# JackPots.net
KiCad netlist of a schematic drawn in EAGLE
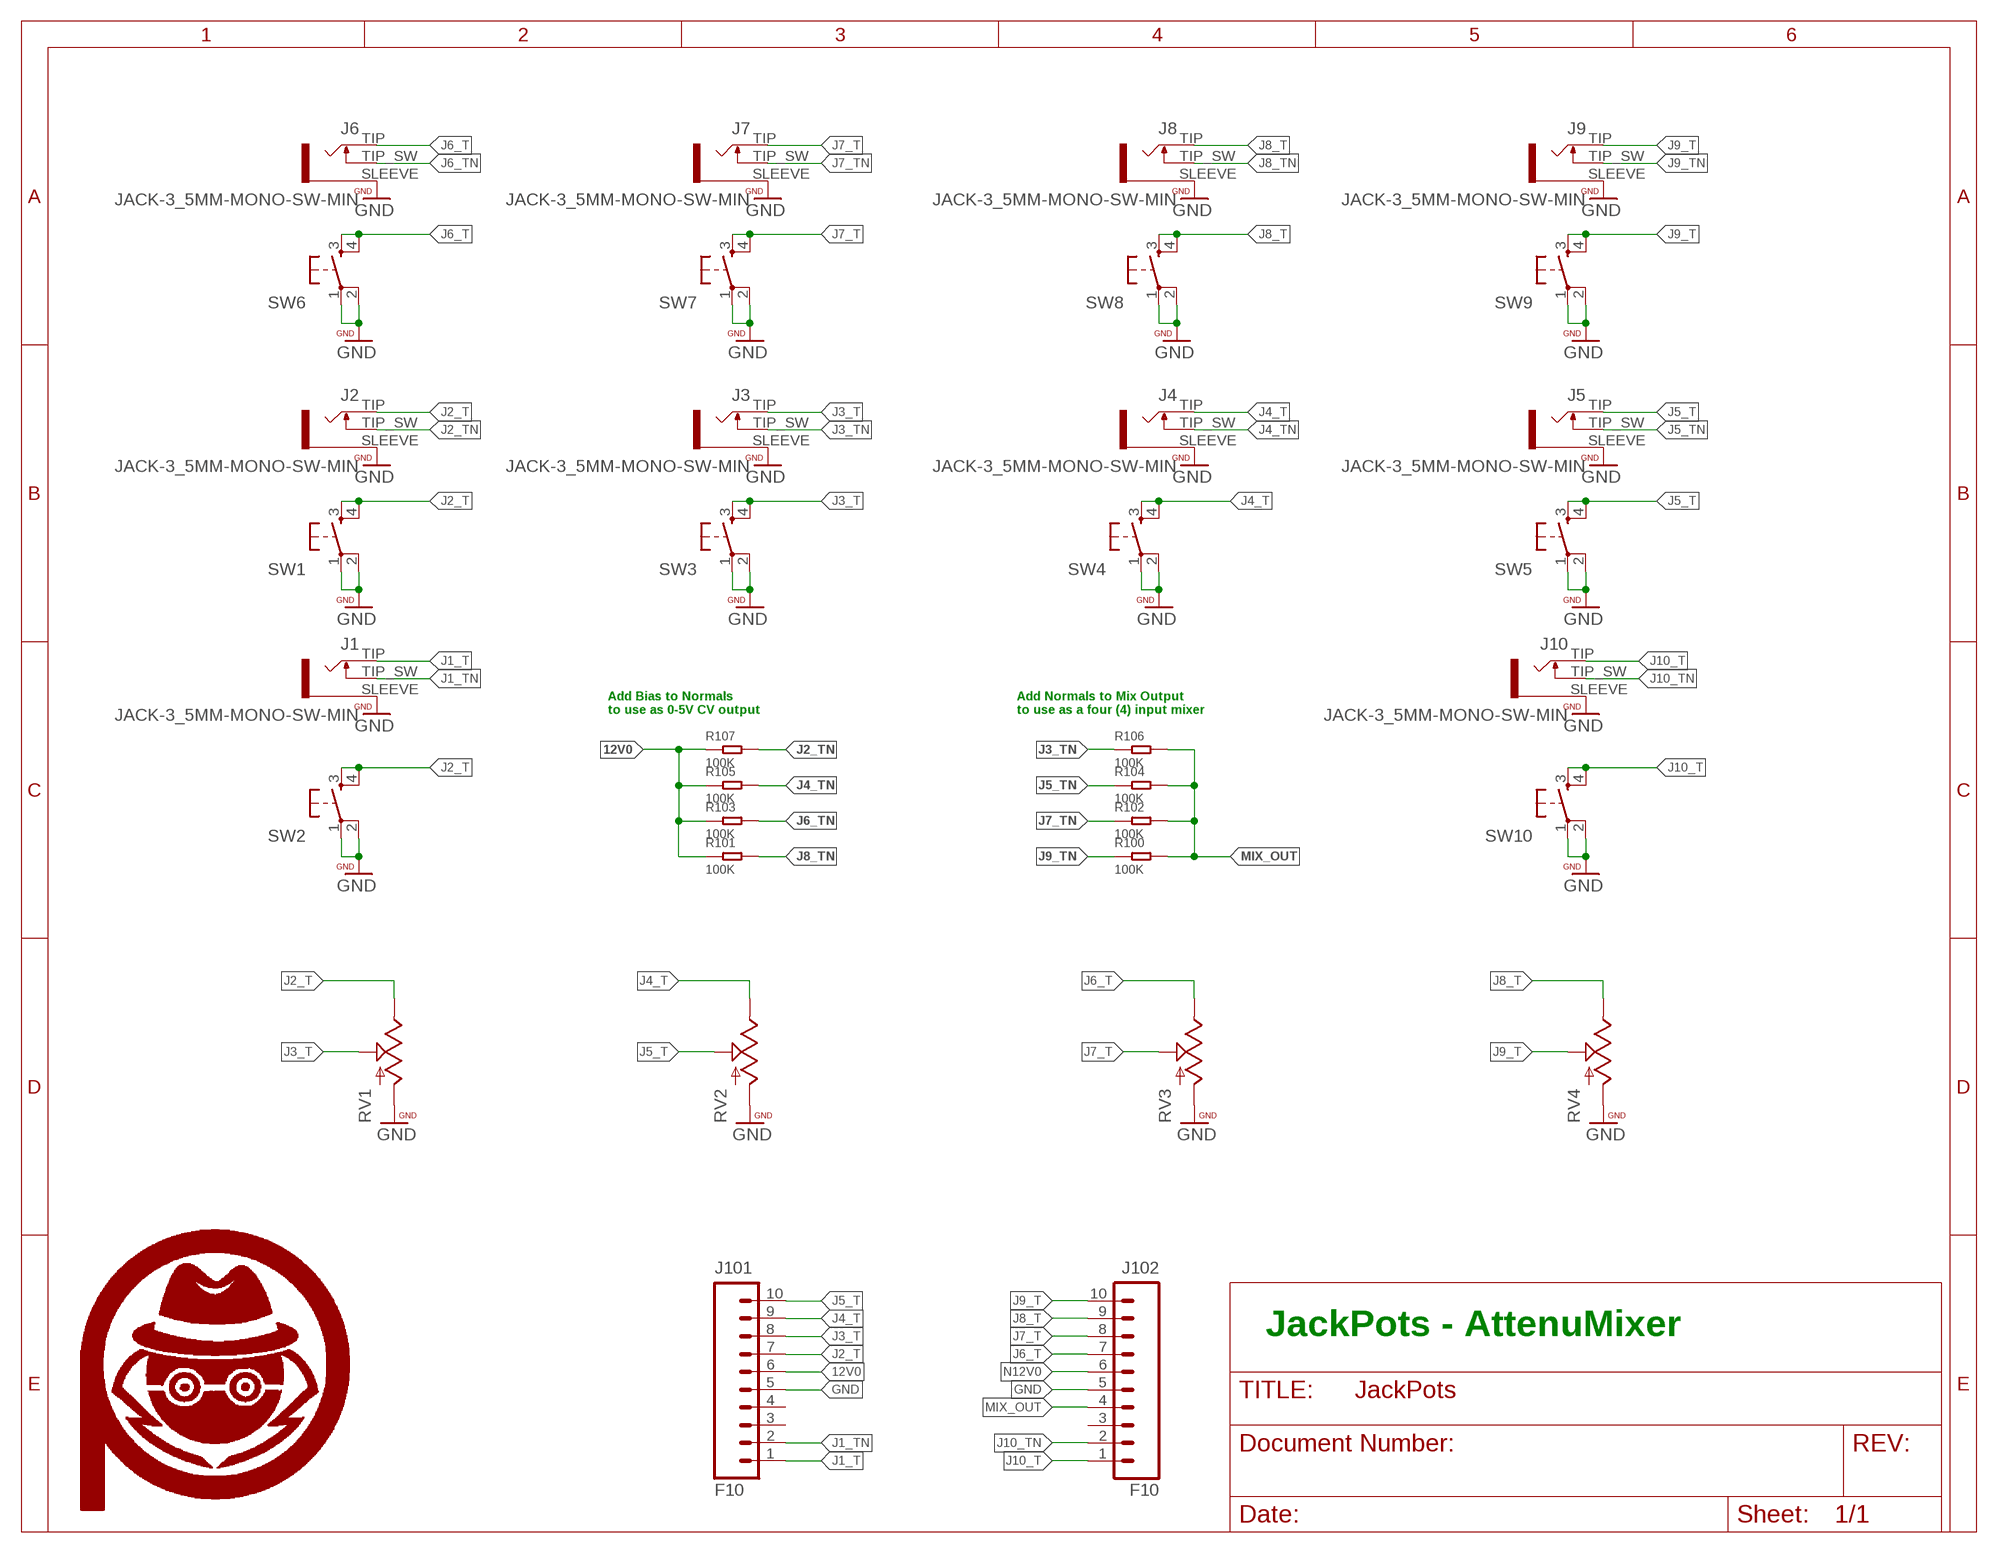
[diagram p0: schematic, sheet 1]

(export (version "E")
  (design (tool "Eeschema 10.0.6"))
  (components
    (comp (ref "$$U$1")
      (value "PA_LOGO_SYMSMALL")
      (footprint "eagle-import:PA_LOGO_AGENT_SMALL_SYM")
      (libsource (lib "eagle-import") (part "PA_LOGO_SYMSMALL"))
    )
    (comp (ref "$$U$100")
      (value "PA_LOGO_SYMMED")
      (footprint "eagle-import:PA_LOGO_AGENT_MED_SYM")
      (libsource (lib "eagle-import") (part "PA_LOGO_SYMMED"))
    )
    (comp (ref "$$U$101")
      (value "PA_LOGO_SYMMED")
      (footprint "eagle-import:PA_LOGO_AGENT_MED_SYM")
      (libsource (lib "eagle-import") (part "PA_LOGO_SYMMED"))
    )
    (comp (ref "J1")
      (value "JACK-3_5MM-MONO-SW-MIN")
      (footprint "eagle-import:WQP_PJ301M-MIN")
      (libsource (lib "eagle-import") (part "JACK-3_5MM-MONO-SW-MIN"))
    )
    (comp (ref "J2")
      (value "JACK-3_5MM-MONO-SW-MIN")
      (footprint "eagle-import:WQP_PJ301M-MIN")
      (libsource (lib "eagle-import") (part "JACK-3_5MM-MONO-SW-MIN"))
    )
    (comp (ref "J3")
      (value "JACK-3_5MM-MONO-SW-MIN")
      (footprint "eagle-import:WQP_PJ301M-MIN")
      (libsource (lib "eagle-import") (part "JACK-3_5MM-MONO-SW-MIN"))
    )
    (comp (ref "J4")
      (value "JACK-3_5MM-MONO-SW-MIN")
      (footprint "eagle-import:WQP_PJ301M-MIN")
      (libsource (lib "eagle-import") (part "JACK-3_5MM-MONO-SW-MIN"))
    )
    (comp (ref "J5")
      (value "JACK-3_5MM-MONO-SW-MIN")
      (footprint "eagle-import:WQP_PJ301M-MIN")
      (libsource (lib "eagle-import") (part "JACK-3_5MM-MONO-SW-MIN"))
    )
    (comp (ref "J6")
      (value "JACK-3_5MM-MONO-SW-MIN")
      (footprint "eagle-import:WQP_PJ301M-MIN")
      (libsource (lib "eagle-import") (part "JACK-3_5MM-MONO-SW-MIN"))
    )
    (comp (ref "J7")
      (value "JACK-3_5MM-MONO-SW-MIN")
      (footprint "eagle-import:WQP_PJ301M-MIN")
      (libsource (lib "eagle-import") (part "JACK-3_5MM-MONO-SW-MIN"))
    )
    (comp (ref "J8")
      (value "JACK-3_5MM-MONO-SW-MIN")
      (footprint "eagle-import:WQP_PJ301M-MIN")
      (libsource (lib "eagle-import") (part "JACK-3_5MM-MONO-SW-MIN"))
    )
    (comp (ref "J9")
      (value "JACK-3_5MM-MONO-SW-MIN")
      (footprint "eagle-import:WQP_PJ301M-MIN")
      (libsource (lib "eagle-import") (part "JACK-3_5MM-MONO-SW-MIN"))
    )
    (comp (ref "J10")
      (value "JACK-3_5MM-MONO-SW-MIN")
      (footprint "eagle-import:WQP_PJ301M-MIN")
      (libsource (lib "eagle-import") (part "JACK-3_5MM-MONO-SW-MIN"))
    )
    (comp (ref "J101")
      (value "F10")
      (footprint "eagle-import:1X10_OCTO")
      (libsource (lib "eagle-import") (part "M10SILK_FEMALE_PTH"))
    )
    (comp (ref "J102")
      (value "F10")
      (footprint "eagle-import:1X10_OCTO")
      (libsource (lib "eagle-import") (part "M10SILK_FEMALE_PTH"))
    )
    (comp (ref "R100")
      (value "100K")
      (footprint "eagle-import:R0603")
      (fields (field (name "MPN") "RC0603FR-07100KL"))
      (libsource (lib "eagle-import") (part "SMD-RES-100K-1%-1/10W(0603)"))
    )
    (comp (ref "R101")
      (value "100K")
      (footprint "eagle-import:R0603")
      (fields (field (name "MPN") "RC0603FR-07100KL"))
      (libsource (lib "eagle-import") (part "SMD-RES-100K-1%-1/10W(0603)"))
    )
    (comp (ref "R102")
      (value "100K")
      (footprint "eagle-import:R0603")
      (fields (field (name "MPN") "RC0603FR-07100KL"))
      (libsource (lib "eagle-import") (part "SMD-RES-100K-1%-1/10W(0603)"))
    )
    (comp (ref "R103")
      (value "100K")
      (footprint "eagle-import:R0603")
      (fields (field (name "MPN") "RC0603FR-07100KL"))
      (libsource (lib "eagle-import") (part "SMD-RES-100K-1%-1/10W(0603)"))
    )
    (comp (ref "R104")
      (value "100K")
      (footprint "eagle-import:R0603")
      (fields (field (name "MPN") "RC0603FR-07100KL"))
      (libsource (lib "eagle-import") (part "SMD-RES-100K-1%-1/10W(0603)"))
    )
    (comp (ref "R105")
      (value "100K")
      (footprint "eagle-import:R0603")
      (fields (field (name "MPN") "RC0603FR-07100KL"))
      (libsource (lib "eagle-import") (part "SMD-RES-100K-1%-1/10W(0603)"))
    )
    (comp (ref "R106")
      (value "100K")
      (footprint "eagle-import:R0603")
      (fields (field (name "MPN") "RC0603FR-07100KL"))
      (libsource (lib "eagle-import") (part "SMD-RES-100K-1%-1/10W(0603)"))
    )
    (comp (ref "R107")
      (value "100K")
      (footprint "eagle-import:R0603")
      (fields (field (name "MPN") "RC0603FR-07100KL"))
      (libsource (lib "eagle-import") (part "SMD-RES-100K-1%-1/10W(0603)"))
    )
    (comp (ref "RV1")
      (value "POT")
      (footprint "eagle-import:ALPS_POT")
      (libsource (lib "eagle-import") (part "POT"))
    )
    (comp (ref "RV2")
      (value "POT")
      (footprint "eagle-import:ALPS_POT")
      (libsource (lib "eagle-import") (part "POT"))
    )
    (comp (ref "RV3")
      (value "POT")
      (footprint "eagle-import:ALPS_POT")
      (libsource (lib "eagle-import") (part "POT"))
    )
    (comp (ref "RV4")
      (value "POT")
      (footprint "eagle-import:ALPS_POT")
      (libsource (lib "eagle-import") (part "POT"))
    )
    (comp (ref "SW1")
      (value "TAC_SWITCHPTH")
      (footprint "eagle-import:TACTILE-PTH")
      (libsource (lib "eagle-import") (part "TAC_SWITCHPTH"))
    )
    (comp (ref "SW2")
      (value "TAC_SWITCHPTH")
      (footprint "eagle-import:TACTILE-PTH")
      (libsource (lib "eagle-import") (part "TAC_SWITCHPTH"))
    )
    (comp (ref "SW3")
      (value "TAC_SWITCHPTH")
      (footprint "eagle-import:TACTILE-PTH")
      (libsource (lib "eagle-import") (part "TAC_SWITCHPTH"))
    )
    (comp (ref "SW4")
      (value "TAC_SWITCHPTH")
      (footprint "eagle-import:TACTILE-PTH")
      (libsource (lib "eagle-import") (part "TAC_SWITCHPTH"))
    )
    (comp (ref "SW5")
      (value "TAC_SWITCHPTH")
      (footprint "eagle-import:TACTILE-PTH")
      (libsource (lib "eagle-import") (part "TAC_SWITCHPTH"))
    )
    (comp (ref "SW6")
      (value "TAC_SWITCHPTH")
      (footprint "eagle-import:TACTILE-PTH")
      (libsource (lib "eagle-import") (part "TAC_SWITCHPTH"))
    )
    (comp (ref "SW7")
      (value "TAC_SWITCHPTH")
      (footprint "eagle-import:TACTILE-PTH")
      (libsource (lib "eagle-import") (part "TAC_SWITCHPTH"))
    )
    (comp (ref "SW8")
      (value "TAC_SWITCHPTH")
      (footprint "eagle-import:TACTILE-PTH")
      (libsource (lib "eagle-import") (part "TAC_SWITCHPTH"))
    )
    (comp (ref "SW9")
      (value "TAC_SWITCHPTH")
      (footprint "eagle-import:TACTILE-PTH")
      (libsource (lib "eagle-import") (part "TAC_SWITCHPTH"))
    )
    (comp (ref "SW10")
      (value "TAC_SWITCHPTH")
      (footprint "eagle-import:TACTILE-PTH")
      (libsource (lib "eagle-import") (part "TAC_SWITCHPTH"))
    )
  )
  (nets
    (net (code "1") (name "12V0") (class "Default")
      (node (ref "J101") (pin "6") (pinfunction "6_6") (pintype "passive"))
      (node (ref "R101") (pin "1") (pinfunction "1_1") (pintype "passive"))
      (node (ref "R103") (pin "1") (pinfunction "1_1") (pintype "passive"))
      (node (ref "R105") (pin "1") (pinfunction "1_1") (pintype "passive"))
      (node (ref "R107") (pin "1") (pinfunction "1_1") (pintype "passive"))
    )
    (net (code "2") (name "GND") (class "Default")
      (node (ref "J1") (pin "SLEEVE") (pinfunction "SLEEVE_SLEEVE") (pintype "passive"))
      (node (ref "J10") (pin "SLEEVE") (pinfunction "SLEEVE_SLEEVE") (pintype "passive"))
      (node (ref "J101") (pin "5") (pinfunction "5_5") (pintype "passive"))
      (node (ref "J102") (pin "5") (pinfunction "5_5") (pintype "passive"))
      (node (ref "J2") (pin "SLEEVE") (pinfunction "SLEEVE_SLEEVE") (pintype "passive"))
      (node (ref "J3") (pin "SLEEVE") (pinfunction "SLEEVE_SLEEVE") (pintype "passive"))
      (node (ref "J4") (pin "SLEEVE") (pinfunction "SLEEVE_SLEEVE") (pintype "passive"))
      (node (ref "J5") (pin "SLEEVE") (pinfunction "SLEEVE_SLEEVE") (pintype "passive"))
      (node (ref "J6") (pin "SLEEVE") (pinfunction "SLEEVE_SLEEVE") (pintype "passive"))
      (node (ref "J7") (pin "SLEEVE") (pinfunction "SLEEVE_SLEEVE") (pintype "passive"))
      (node (ref "J8") (pin "SLEEVE") (pinfunction "SLEEVE_SLEEVE") (pintype "passive"))
      (node (ref "J9") (pin "SLEEVE") (pinfunction "SLEEVE_SLEEVE") (pintype "passive"))
      (node (ref "RV1") (pin "P$3") (pinfunction "1_P$3") (pintype "passive"))
      (node (ref "RV2") (pin "P$3") (pinfunction "1_P$3") (pintype "passive"))
      (node (ref "RV3") (pin "P$3") (pinfunction "1_P$3") (pintype "passive"))
      (node (ref "RV4") (pin "P$3") (pinfunction "1_P$3") (pintype "passive"))
      (node (ref "SW1") (pin "1") (pinfunction "1_1") (pintype "passive"))
      (node (ref "SW1") (pin "2") (pinfunction "2_2") (pintype "passive"))
      (node (ref "SW10") (pin "1") (pinfunction "1_1") (pintype "passive"))
      (node (ref "SW10") (pin "2") (pinfunction "2_2") (pintype "passive"))
      (node (ref "SW2") (pin "1") (pinfunction "1_1") (pintype "passive"))
      (node (ref "SW2") (pin "2") (pinfunction "2_2") (pintype "passive"))
      (node (ref "SW3") (pin "1") (pinfunction "1_1") (pintype "passive"))
      (node (ref "SW3") (pin "2") (pinfunction "2_2") (pintype "passive"))
      (node (ref "SW4") (pin "1") (pinfunction "1_1") (pintype "passive"))
      (node (ref "SW4") (pin "2") (pinfunction "2_2") (pintype "passive"))
      (node (ref "SW5") (pin "1") (pinfunction "1_1") (pintype "passive"))
      (node (ref "SW5") (pin "2") (pinfunction "2_2") (pintype "passive"))
      (node (ref "SW6") (pin "1") (pinfunction "1_1") (pintype "passive"))
      (node (ref "SW6") (pin "2") (pinfunction "2_2") (pintype "passive"))
      (node (ref "SW7") (pin "1") (pinfunction "1_1") (pintype "passive"))
      (node (ref "SW7") (pin "2") (pinfunction "2_2") (pintype "passive"))
      (node (ref "SW8") (pin "1") (pinfunction "1_1") (pintype "passive"))
      (node (ref "SW8") (pin "2") (pinfunction "2_2") (pintype "passive"))
      (node (ref "SW9") (pin "1") (pinfunction "1_1") (pintype "passive"))
      (node (ref "SW9") (pin "2") (pinfunction "2_2") (pintype "passive"))
    )
    (net (code "3") (name "J1_T") (class "Default")
      (node (ref "J1") (pin "TIP") (pinfunction "TIP_TIP") (pintype "passive"))
      (node (ref "J101") (pin "1") (pinfunction "1_1") (pintype "passive"))
    )
    (net (code "4") (name "J1_TN") (class "Default")
      (node (ref "J1") (pin "TIP_SW") (pinfunction "TIP_SW_TIP_SW") (pintype "passive"))
      (node (ref "J101") (pin "2") (pinfunction "2_2") (pintype "passive"))
    )
    (net (code "5") (name "J2_T") (class "Default")
      (node (ref "J101") (pin "7") (pinfunction "7_7") (pintype "passive"))
      (node (ref "J2") (pin "TIP") (pinfunction "TIP_TIP") (pintype "passive"))
      (node (ref "RV1") (pin "P$1") (pinfunction "3_P$1") (pintype "passive"))
      (node (ref "SW1") (pin "3") (pinfunction "3_3") (pintype "passive"))
      (node (ref "SW1") (pin "4") (pinfunction "4_4") (pintype "passive"))
      (node (ref "SW2") (pin "3") (pinfunction "3_3") (pintype "passive"))
      (node (ref "SW2") (pin "4") (pinfunction "4_4") (pintype "passive"))
    )
    (net (code "6") (name "J2_TN") (class "Default")
      (node (ref "J2") (pin "TIP_SW") (pinfunction "TIP_SW_TIP_SW") (pintype "passive"))
      (node (ref "R107") (pin "2") (pinfunction "2_2") (pintype "passive"))
    )
    (net (code "7") (name "J3_T") (class "Default")
      (node (ref "J101") (pin "8") (pinfunction "8_8") (pintype "passive"))
      (node (ref "J3") (pin "TIP") (pinfunction "TIP_TIP") (pintype "passive"))
      (node (ref "RV1") (pin "P$2") (pinfunction "2_P$2") (pintype "passive"))
      (node (ref "SW3") (pin "3") (pinfunction "3_3") (pintype "passive"))
      (node (ref "SW3") (pin "4") (pinfunction "4_4") (pintype "passive"))
    )
    (net (code "8") (name "J3_TN") (class "Default")
      (node (ref "J3") (pin "TIP_SW") (pinfunction "TIP_SW_TIP_SW") (pintype "passive"))
      (node (ref "R106") (pin "1") (pinfunction "1_1") (pintype "passive"))
    )
    (net (code "9") (name "J4_T") (class "Default")
      (node (ref "J101") (pin "9") (pinfunction "9_9") (pintype "passive"))
      (node (ref "J4") (pin "TIP") (pinfunction "TIP_TIP") (pintype "passive"))
      (node (ref "RV2") (pin "P$1") (pinfunction "3_P$1") (pintype "passive"))
      (node (ref "SW4") (pin "3") (pinfunction "3_3") (pintype "passive"))
      (node (ref "SW4") (pin "4") (pinfunction "4_4") (pintype "passive"))
    )
    (net (code "10") (name "J4_TN") (class "Default")
      (node (ref "J4") (pin "TIP_SW") (pinfunction "TIP_SW_TIP_SW") (pintype "passive"))
      (node (ref "R105") (pin "2") (pinfunction "2_2") (pintype "passive"))
    )
    (net (code "11") (name "J5_T") (class "Default")
      (node (ref "J101") (pin "10") (pinfunction "10_10") (pintype "passive"))
      (node (ref "J5") (pin "TIP") (pinfunction "TIP_TIP") (pintype "passive"))
      (node (ref "RV2") (pin "P$2") (pinfunction "2_P$2") (pintype "passive"))
      (node (ref "SW5") (pin "3") (pinfunction "3_3") (pintype "passive"))
      (node (ref "SW5") (pin "4") (pinfunction "4_4") (pintype "passive"))
    )
    (net (code "12") (name "J5_TN") (class "Default")
      (node (ref "J5") (pin "TIP_SW") (pinfunction "TIP_SW_TIP_SW") (pintype "passive"))
      (node (ref "R104") (pin "1") (pinfunction "1_1") (pintype "passive"))
    )
    (net (code "13") (name "J6_T") (class "Default")
      (node (ref "J102") (pin "7") (pinfunction "7_7") (pintype "passive"))
      (node (ref "J6") (pin "TIP") (pinfunction "TIP_TIP") (pintype "passive"))
      (node (ref "RV3") (pin "P$1") (pinfunction "3_P$1") (pintype "passive"))
      (node (ref "SW6") (pin "3") (pinfunction "3_3") (pintype "passive"))
      (node (ref "SW6") (pin "4") (pinfunction "4_4") (pintype "passive"))
    )
    (net (code "14") (name "J6_TN") (class "Default")
      (node (ref "J6") (pin "TIP_SW") (pinfunction "TIP_SW_TIP_SW") (pintype "passive"))
      (node (ref "R103") (pin "2") (pinfunction "2_2") (pintype "passive"))
    )
    (net (code "15") (name "J7_T") (class "Default")
      (node (ref "J102") (pin "8") (pinfunction "8_8") (pintype "passive"))
      (node (ref "J7") (pin "TIP") (pinfunction "TIP_TIP") (pintype "passive"))
      (node (ref "RV3") (pin "P$2") (pinfunction "2_P$2") (pintype "passive"))
      (node (ref "SW7") (pin "3") (pinfunction "3_3") (pintype "passive"))
      (node (ref "SW7") (pin "4") (pinfunction "4_4") (pintype "passive"))
    )
    (net (code "16") (name "J7_TN") (class "Default")
      (node (ref "J7") (pin "TIP_SW") (pinfunction "TIP_SW_TIP_SW") (pintype "passive"))
      (node (ref "R102") (pin "1") (pinfunction "1_1") (pintype "passive"))
    )
    (net (code "17") (name "J8_T") (class "Default")
      (node (ref "J102") (pin "9") (pinfunction "9_9") (pintype "passive"))
      (node (ref "J8") (pin "TIP") (pinfunction "TIP_TIP") (pintype "passive"))
      (node (ref "RV4") (pin "P$1") (pinfunction "3_P$1") (pintype "passive"))
      (node (ref "SW8") (pin "3") (pinfunction "3_3") (pintype "passive"))
      (node (ref "SW8") (pin "4") (pinfunction "4_4") (pintype "passive"))
    )
    (net (code "18") (name "J8_TN") (class "Default")
      (node (ref "J8") (pin "TIP_SW") (pinfunction "TIP_SW_TIP_SW") (pintype "passive"))
      (node (ref "R101") (pin "2") (pinfunction "2_2") (pintype "passive"))
    )
    (net (code "19") (name "J9_T") (class "Default")
      (node (ref "J102") (pin "10") (pinfunction "10_10") (pintype "passive"))
      (node (ref "J9") (pin "TIP") (pinfunction "TIP_TIP") (pintype "passive"))
      (node (ref "RV4") (pin "P$2") (pinfunction "2_P$2") (pintype "passive"))
      (node (ref "SW9") (pin "3") (pinfunction "3_3") (pintype "passive"))
      (node (ref "SW9") (pin "4") (pinfunction "4_4") (pintype "passive"))
    )
    (net (code "20") (name "J9_TN") (class "Default")
      (node (ref "J9") (pin "TIP_SW") (pinfunction "TIP_SW_TIP_SW") (pintype "passive"))
      (node (ref "R100") (pin "1") (pinfunction "1_1") (pintype "passive"))
    )
    (net (code "21") (name "J10_T") (class "Default")
      (node (ref "J10") (pin "TIP") (pinfunction "TIP_TIP") (pintype "passive"))
      (node (ref "J102") (pin "1") (pinfunction "1_1") (pintype "passive"))
      (node (ref "SW10") (pin "3") (pinfunction "3_3") (pintype "passive"))
      (node (ref "SW10") (pin "4") (pinfunction "4_4") (pintype "passive"))
    )
    (net (code "22") (name "J10_TN") (class "Default")
      (node (ref "J10") (pin "TIP_SW") (pinfunction "TIP_SW_TIP_SW") (pintype "passive"))
      (node (ref "J102") (pin "2") (pinfunction "2_2") (pintype "passive"))
    )
    (net (code "23") (name "MIX_OUT") (class "Default")
      (node (ref "J102") (pin "4") (pinfunction "4_4") (pintype "passive"))
      (node (ref "R100") (pin "2") (pinfunction "2_2") (pintype "passive"))
      (node (ref "R102") (pin "2") (pinfunction "2_2") (pintype "passive"))
      (node (ref "R104") (pin "2") (pinfunction "2_2") (pintype "passive"))
      (node (ref "R106") (pin "2") (pinfunction "2_2") (pintype "passive"))
    )
    (net (code "24") (name "N12V0") (class "Default")
      (node (ref "J102") (pin "6") (pinfunction "6_6") (pintype "passive"))
    )
    (net (code "25") (name "unconnected-(J101-Pad3)") (class "Default")
      (node (ref "J101") (pin "3") (pinfunction "3_3") (pintype "passive"))
    )
    (net (code "26") (name "unconnected-(J101-Pad4)") (class "Default")
      (node (ref "J101") (pin "4") (pinfunction "4_4") (pintype "passive"))
    )
    (net (code "27") (name "unconnected-(J102-Pad3)") (class "Default")
      (node (ref "J102") (pin "3") (pinfunction "3_3") (pintype "passive"))
    )
  )
)
